# JTAG.net
KiCad netlist of a schematic drawn in Altium Designer
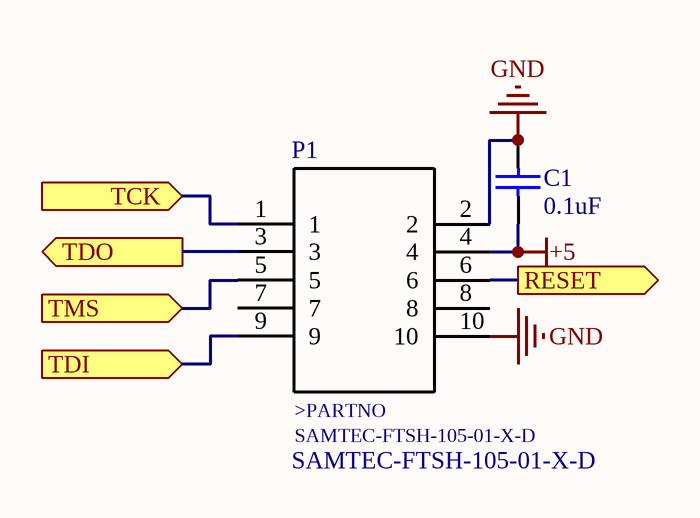
[diagram p0: JTAG.SchDoc]

(export (version "E")
  (design (tool "Eeschema 10.0.6"))
  (components
    (comp (ref "C1")
      (value "0.1uF")
      (footprint "CAPC2013X94X50LL20T25")
      (description "Chip Capacitor, 0.1 uF, +/- 5%, 50 V, -55 to 125 degC, 0805 (2012 Metric), RoHS, Tape and Reel")
      (fields (field (name "TOLERANCE") "5%") (field (name "MANUFACTURER") "AVX"))
      (libsource (lib "Altium Content Vault") (part "CAP-NP-2"))
    )
    (comp (ref "P1")
      (value "SAMTEC-FTSH-105-01-X-D")
      (footprint "SAMTEC-FTSH-105-01-X-D")
      (libsource (lib "Husky Robotics Standard Library 2019-2020") (part "SAMTEC-FTSH-105-01-X-D"))
    )
  )
  (nets
    (net (code "1") (name "+5") (class "Default")
      (node (ref "C1") (pin "1") (pinfunction "1_1") (pintype "passive"))
      (node (ref "P1") (pin "4") (pinfunction "4_4") (pintype "passive"))
    )
    (net (code "2") (name "/RESET") (class "Default")
      (node (ref "P1") (pin "6") (pinfunction "6_6") (pintype "passive"))
    )
    (net (code "3") (name "/TCK") (class "Default")
      (node (ref "P1") (pin "1") (pinfunction "1_1") (pintype "passive"))
    )
    (net (code "4") (name "/TDI") (class "Default")
      (node (ref "P1") (pin "9") (pinfunction "9_9") (pintype "passive"))
    )
    (net (code "5") (name "/TDO") (class "Default")
      (node (ref "P1") (pin "3") (pinfunction "3_3") (pintype "passive"))
    )
    (net (code "6") (name "/TMS") (class "Default")
      (node (ref "P1") (pin "5") (pinfunction "5_5") (pintype "passive"))
    )
    (net (code "7") (name "GND") (class "Default")
      (node (ref "C1") (pin "2") (pinfunction "2_2") (pintype "passive"))
      (node (ref "P1") (pin "10") (pinfunction "10_10") (pintype "passive"))
      (node (ref "P1") (pin "2") (pinfunction "2_2") (pintype "passive"))
    )
    (net (code "8") (name "unconnected-(P1-Pad7)") (class "Default")
      (node (ref "P1") (pin "7") (pinfunction "7_7") (pintype "passive"))
    )
    (net (code "9") (name "unconnected-(P1-Pad8)") (class "Default")
      (node (ref "P1") (pin "8") (pinfunction "8_8") (pintype "passive"))
    )
  )
)
